# control.net
KiCad netlist of a schematic drawn in EAGLE
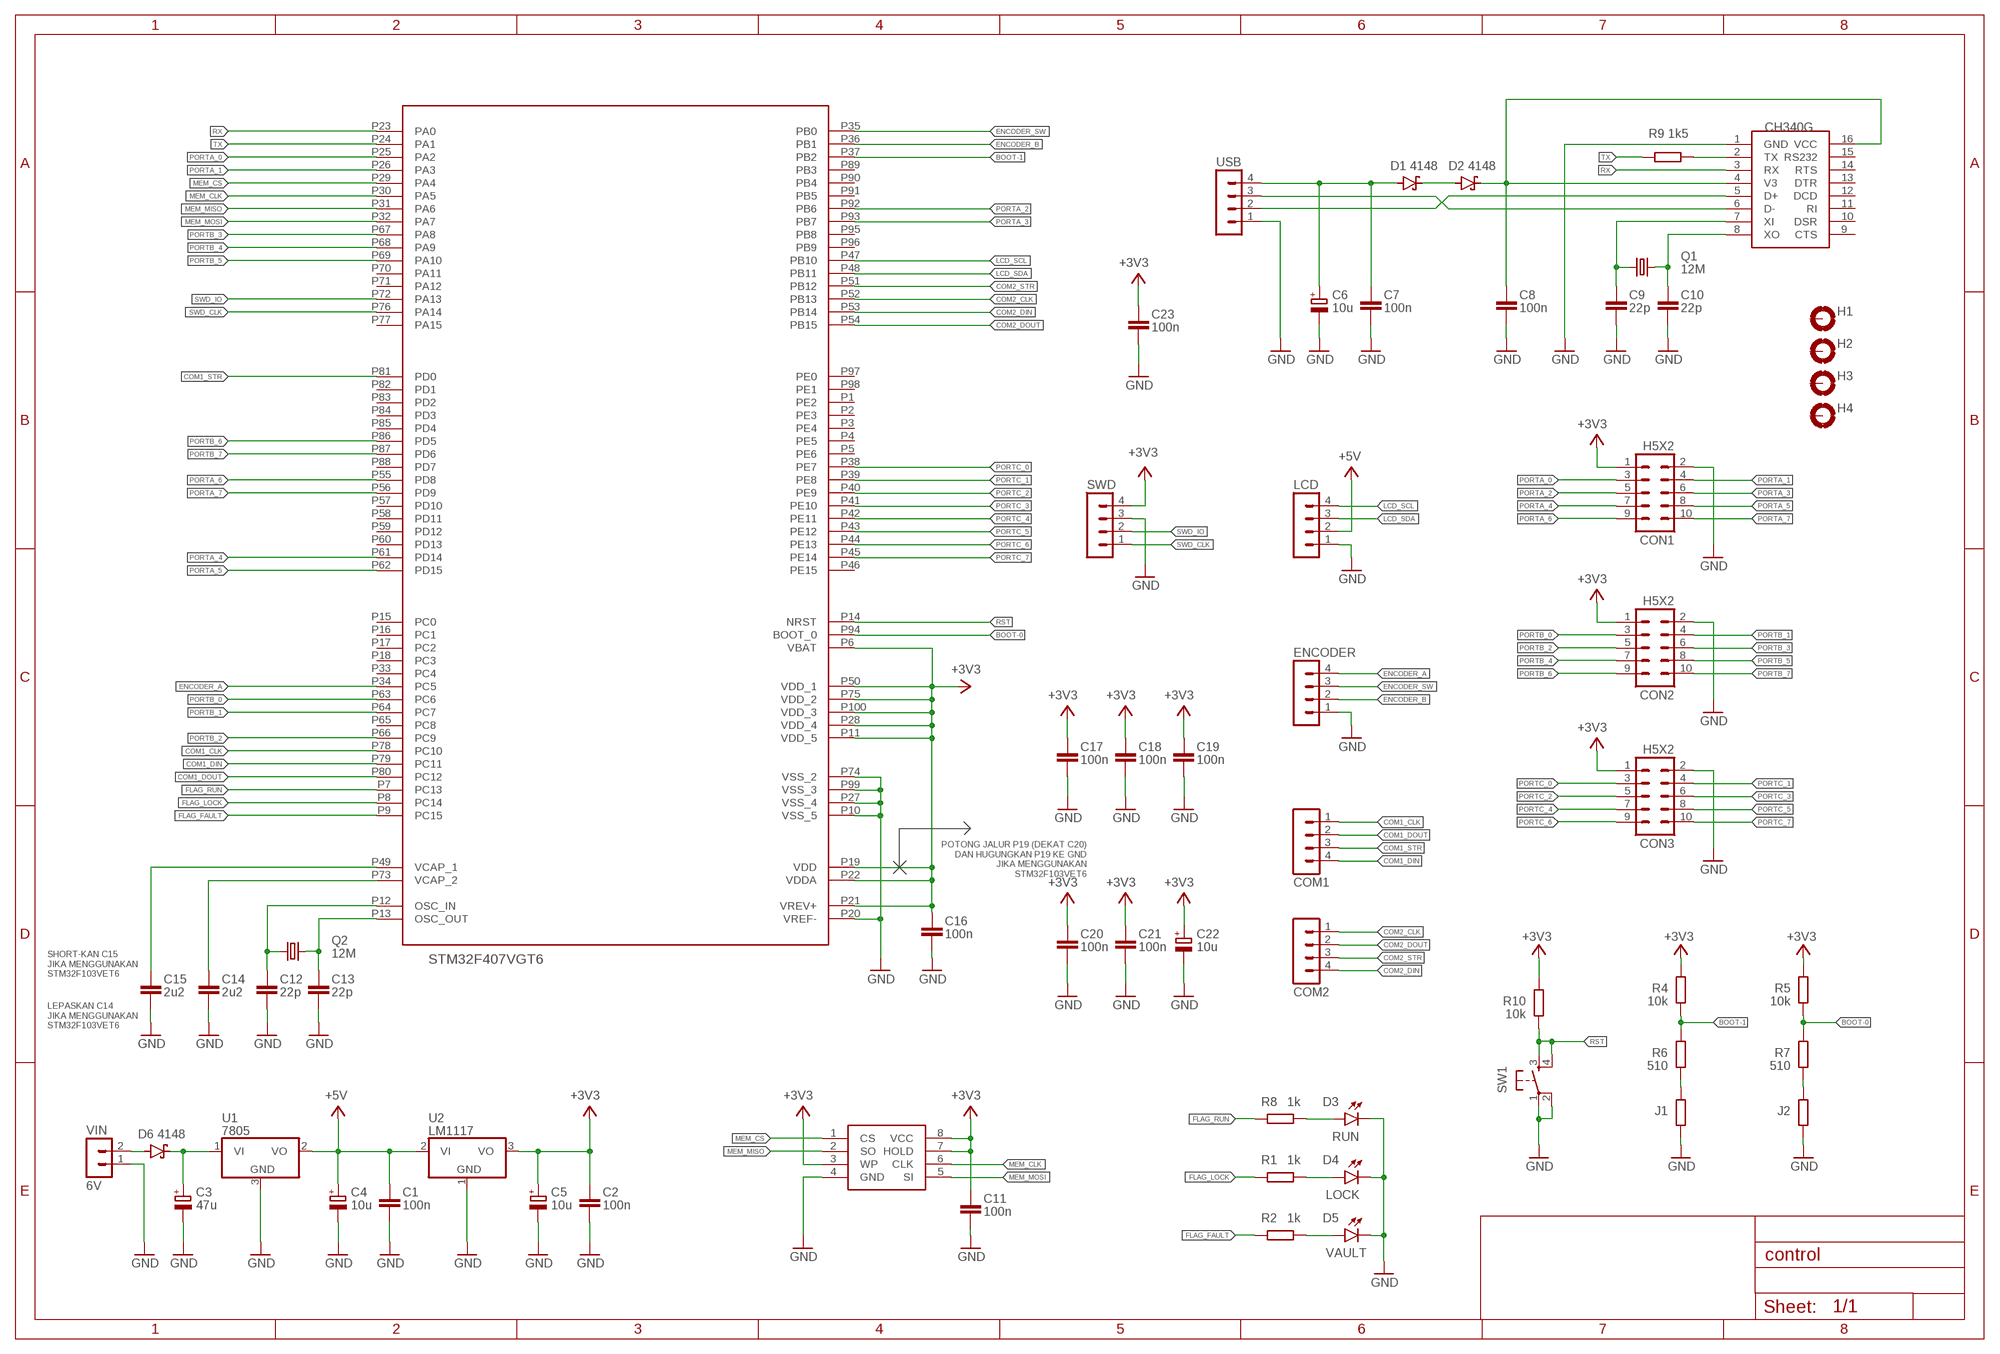
[diagram p0: schematic, sheet 1]

(export (version "E")
  (design (tool "Eeschema 10.0.6"))
  (components
    (comp (ref "C1")
      (value "100n")
      (footprint "eagle-import:0805")
      (libsource (lib "eagle-import") (part "CAP"))
    )
    (comp (ref "C2")
      (value "100n")
      (footprint "eagle-import:0805")
      (libsource (lib "eagle-import") (part "CAP"))
    )
    (comp (ref "C3")
      (value "47u")
      (footprint "eagle-import:E2,5-5")
      (libsource (lib "eagle-import") (part "C10UF"))
    )
    (comp (ref "C4")
      (value "10u")
      (footprint "eagle-import:E2,5-5")
      (libsource (lib "eagle-import") (part "C10UF"))
    )
    (comp (ref "C5")
      (value "10u")
      (footprint "eagle-import:E2,5-5")
      (libsource (lib "eagle-import") (part "C10UF"))
    )
    (comp (ref "C6")
      (value "10u")
      (footprint "eagle-import:E2,5-5")
      (libsource (lib "eagle-import") (part "C10UF"))
    )
    (comp (ref "C7")
      (value "100n")
      (footprint "eagle-import:0805")
      (libsource (lib "eagle-import") (part "CAP"))
    )
    (comp (ref "C8")
      (value "100n")
      (footprint "eagle-import:0805")
      (libsource (lib "eagle-import") (part "CAP"))
    )
    (comp (ref "C9")
      (value "22p")
      (footprint "eagle-import:0805")
      (libsource (lib "eagle-import") (part "CAP"))
    )
    (comp (ref "C10")
      (value "22p")
      (footprint "eagle-import:0805")
      (libsource (lib "eagle-import") (part "CAP"))
    )
    (comp (ref "C11")
      (value "100n")
      (footprint "eagle-import:0805")
      (libsource (lib "eagle-import") (part "CAP"))
    )
    (comp (ref "C12")
      (value "22p")
      (footprint "eagle-import:0805")
      (libsource (lib "eagle-import") (part "CAP"))
    )
    (comp (ref "C13")
      (value "22p")
      (footprint "eagle-import:0805")
      (libsource (lib "eagle-import") (part "CAP"))
    )
    (comp (ref "C14")
      (value "2u2")
      (footprint "eagle-import:0805")
      (libsource (lib "eagle-import") (part "CAP"))
    )
    (comp (ref "C15")
      (value "2u2")
      (footprint "eagle-import:0805")
      (libsource (lib "eagle-import") (part "CAP"))
    )
    (comp (ref "C16")
      (value "100n")
      (footprint "eagle-import:0805")
      (libsource (lib "eagle-import") (part "CAP"))
    )
    (comp (ref "C17")
      (value "100n")
      (footprint "eagle-import:0805")
      (libsource (lib "eagle-import") (part "CAP"))
    )
    (comp (ref "C18")
      (value "100n")
      (footprint "eagle-import:0805")
      (libsource (lib "eagle-import") (part "CAP"))
    )
    (comp (ref "C19")
      (value "100n")
      (footprint "eagle-import:0805")
      (libsource (lib "eagle-import") (part "CAP"))
    )
    (comp (ref "C20")
      (value "100n")
      (footprint "eagle-import:0805")
      (libsource (lib "eagle-import") (part "CAP"))
    )
    (comp (ref "C21")
      (value "100n")
      (footprint "eagle-import:0805")
      (libsource (lib "eagle-import") (part "CAP"))
    )
    (comp (ref "C22")
      (value "10u")
      (footprint "eagle-import:E2,5-5")
      (libsource (lib "eagle-import") (part "C10UF"))
    )
    (comp (ref "C23")
      (value "100n")
      (footprint "eagle-import:0805")
      (libsource (lib "eagle-import") (part "CAP"))
    )
    (comp (ref "COM1")
      (value "MOLEX-4")
      (footprint "eagle-import:6410-04")
      (libsource (lib "eagle-import") (part "MOLEX-4"))
    )
    (comp (ref "COM2")
      (value "MOLEX-4")
      (footprint "eagle-import:6410-04")
      (libsource (lib "eagle-import") (part "MOLEX-4"))
    )
    (comp (ref "CON1")
      (value "H5X2")
      (footprint "eagle-import:MA05-2")
      (libsource (lib "eagle-import") (part "H5X2"))
    )
    (comp (ref "CON2")
      (value "H5X2")
      (footprint "eagle-import:MA05-2")
      (libsource (lib "eagle-import") (part "H5X2"))
    )
    (comp (ref "CON3")
      (value "H5X2")
      (footprint "eagle-import:MA05-2")
      (libsource (lib "eagle-import") (part "H5X2"))
    )
    (comp (ref "D1")
      (value "4148")
      (footprint "eagle-import:DO35Z7")
      (libsource (lib "eagle-import") (part "1N5817"))
    )
    (comp (ref "D2")
      (value "4148")
      (footprint "eagle-import:DO35Z7")
      (libsource (lib "eagle-import") (part "1N5817"))
    )
    (comp (ref "D3")
      (value "RUN")
      (footprint "eagle-import:LED3MM")
      (libsource (lib "eagle-import") (part "LED3MM"))
    )
    (comp (ref "D4")
      (value "LOCK")
      (footprint "eagle-import:LED3MM")
      (libsource (lib "eagle-import") (part "LED3MM"))
    )
    (comp (ref "D5")
      (value "VAULT")
      (footprint "eagle-import:LED3MM")
      (libsource (lib "eagle-import") (part "LED3MM"))
    )
    (comp (ref "D6")
      (value "4148")
      (footprint "eagle-import:DO35Z7")
      (libsource (lib "eagle-import") (part "1N5817"))
    )
    (comp (ref "ENCODER")
      (value "MOLEX-4")
      (footprint "eagle-import:6410-04")
      (libsource (lib "eagle-import") (part "MOLEX-4"))
    )
    (comp (ref "H1")
      (value "MOUNT-PAD-ROUND3.0")
      (footprint "eagle-import:3,0-PAD")
      (libsource (lib "eagle-import") (part "MOUNT-PAD-ROUND3.0"))
    )
    (comp (ref "H2")
      (value "MOUNT-PAD-ROUND3.0")
      (footprint "eagle-import:3,0-PAD")
      (libsource (lib "eagle-import") (part "MOUNT-PAD-ROUND3.0"))
    )
    (comp (ref "H3")
      (value "MOUNT-PAD-ROUND3.0")
      (footprint "eagle-import:3,0-PAD")
      (libsource (lib "eagle-import") (part "MOUNT-PAD-ROUND3.0"))
    )
    (comp (ref "H4")
      (value "MOUNT-PAD-ROUND3.0")
      (footprint "eagle-import:3,0-PAD")
      (libsource (lib "eagle-import") (part "MOUNT-PAD-ROUND3.0"))
    )
    (comp (ref "J1")
      (value "10k")
      (footprint "eagle-import:0805")
      (libsource (lib "eagle-import") (part "RES"))
    )
    (comp (ref "J2")
      (value "10k")
      (footprint "eagle-import:0805")
      (libsource (lib "eagle-import") (part "RES"))
    )
    (comp (ref "LCD")
      (value "MOLEX-4")
      (footprint "eagle-import:6410-04")
      (libsource (lib "eagle-import") (part "MOLEX-4"))
    )
    (comp (ref "Q1")
      (value "12M")
      (footprint "eagle-import:HC49_S")
      (libsource (lib "eagle-import") (part "CRYSTAL"))
    )
    (comp (ref "Q2")
      (value "12M")
      (footprint "eagle-import:HC49_S")
      (libsource (lib "eagle-import") (part "CRYSTAL"))
    )
    (comp (ref "R1")
      (value "1k")
      (footprint "eagle-import:0805")
      (libsource (lib "eagle-import") (part "RES"))
    )
    (comp (ref "R2")
      (value "1k")
      (footprint "eagle-import:0805")
      (libsource (lib "eagle-import") (part "RES"))
    )
    (comp (ref "R4")
      (value "10k")
      (footprint "eagle-import:0805")
      (libsource (lib "eagle-import") (part "RES"))
    )
    (comp (ref "R5")
      (value "10k")
      (footprint "eagle-import:0805")
      (libsource (lib "eagle-import") (part "RES"))
    )
    (comp (ref "R6")
      (value "510")
      (footprint "eagle-import:0805")
      (libsource (lib "eagle-import") (part "RES"))
    )
    (comp (ref "R7")
      (value "510")
      (footprint "eagle-import:0805")
      (libsource (lib "eagle-import") (part "RES"))
    )
    (comp (ref "R8")
      (value "1k")
      (footprint "eagle-import:0805")
      (libsource (lib "eagle-import") (part "RES"))
    )
    (comp (ref "R9")
      (value "1k5")
      (footprint "eagle-import:0204_7")
      (libsource (lib "eagle-import") (part "R025"))
    )
    (comp (ref "R10")
      (value "10k")
      (footprint "eagle-import:0805")
      (libsource (lib "eagle-import") (part "RES"))
    )
    (comp (ref "SW1")
      (value "SW")
      (footprint "eagle-import:B3F-10XX")
      (libsource (lib "eagle-import") (part "SW"))
    )
    (comp (ref "SWD")
      (value "MOLEX-4")
      (footprint "eagle-import:6410-04")
      (libsource (lib "eagle-import") (part "MOLEX-4"))
    )
    (comp (ref "U$1")
      (value "CH340G")
      (footprint "eagle-import:SOIC16")
      (libsource (lib "eagle-import") (part "CH340G"))
    )
    (comp (ref "U1")
      (value "7805")
      (footprint "eagle-import:TO252")
      (libsource (lib "eagle-import") (part "7805"))
    )
    (comp (ref "U2")
      (value "LM1117")
      (footprint "eagle-import:TO252")
      (libsource (lib "eagle-import") (part "LM1117"))
    )
    (comp (ref "U3")
      (value "W25QXX")
      (footprint "eagle-import:SOP8")
      (libsource (lib "eagle-import") (part "W25QXX"))
    )
    (comp (ref "U4")
      (value "STM32F407")
      (footprint "eagle-import:LQFP100")
      (libsource (lib "eagle-import") (part "STM32F407"))
    )
    (comp (ref "USB")
      (value "MOLEX-4")
      (footprint "eagle-import:6410-04")
      (libsource (lib "eagle-import") (part "MOLEX-4"))
    )
    (comp (ref "VIN")
      (value "6V")
      (footprint "eagle-import:6410-02")
      (libsource (lib "eagle-import") (part "MOLEX-2"))
    )
  )
  (nets
    (net (code "1") (name "+3V3") (class "Default")
      (node (ref "C11") (pin "P$1") (pinfunction "1_P$1") (pintype "passive"))
      (node (ref "C16") (pin "P$1") (pinfunction "1_P$1") (pintype "passive"))
      (node (ref "C17") (pin "P$1") (pinfunction "1_P$1") (pintype "passive"))
      (node (ref "C18") (pin "P$1") (pinfunction "1_P$1") (pintype "passive"))
      (node (ref "C19") (pin "P$1") (pinfunction "1_P$1") (pintype "passive"))
      (node (ref "C2") (pin "P$1") (pinfunction "1_P$1") (pintype "passive"))
      (node (ref "C20") (pin "P$1") (pinfunction "1_P$1") (pintype "passive"))
      (node (ref "C21") (pin "P$1") (pinfunction "1_P$1") (pintype "passive"))
      (node (ref "C22") (pin "+") (pinfunction "+_+") (pintype "passive"))
      (node (ref "C23") (pin "P$1") (pinfunction "1_P$1") (pintype "passive"))
      (node (ref "C5") (pin "+") (pinfunction "+_+") (pintype "passive"))
      (node (ref "CON1") (pin "1") (pinfunction "1_1") (pintype "passive"))
      (node (ref "CON2") (pin "1") (pinfunction "1_1") (pintype "passive"))
      (node (ref "CON3") (pin "1") (pinfunction "1_1") (pintype "passive"))
      (node (ref "R10") (pin "P$2") (pinfunction "2_P$2") (pintype "passive"))
      (node (ref "R4") (pin "P$2") (pinfunction "2_P$2") (pintype "passive"))
      (node (ref "R5") (pin "P$2") (pinfunction "2_P$2") (pintype "passive"))
      (node (ref "SWD") (pin "4") (pinfunction "4_4") (pintype "passive"))
      (node (ref "U2") (pin "3") (pinfunction "VO_3") (pintype "passive"))
      (node (ref "U3") (pin "3") (pinfunction "WP_3") (pintype "bidirectional"))
      (node (ref "U3") (pin "7") (pinfunction "HOLD_7") (pintype "bidirectional"))
      (node (ref "U3") (pin "8") (pinfunction "VCC_8") (pintype "bidirectional"))
      (node (ref "U4") (pin "P100") (pinfunction "VDD_3_P100") (pintype "bidirectional"))
      (node (ref "U4") (pin "P11") (pinfunction "VDD_5_P11") (pintype "bidirectional"))
      (node (ref "U4") (pin "P19") (pinfunction "VDD_P19") (pintype "bidirectional"))
      (node (ref "U4") (pin "P21") (pinfunction "VREV+_P21") (pintype "bidirectional"))
      (node (ref "U4") (pin "P22") (pinfunction "VDDA_P22") (pintype "bidirectional"))
      (node (ref "U4") (pin "P28") (pinfunction "VDD_4_P28") (pintype "bidirectional"))
      (node (ref "U4") (pin "P50") (pinfunction "VDD_1_P50") (pintype "bidirectional"))
      (node (ref "U4") (pin "P6") (pinfunction "VBAT_P6") (pintype "bidirectional"))
      (node (ref "U4") (pin "P75") (pinfunction "VDD_2_P75") (pintype "bidirectional"))
    )
    (net (code "2") (name "+5V") (class "Default")
      (node (ref "C1") (pin "P$1") (pinfunction "1_P$1") (pintype "passive"))
      (node (ref "C4") (pin "+") (pinfunction "+_+") (pintype "passive"))
      (node (ref "LCD") (pin "2") (pinfunction "2_2") (pintype "passive"))
      (node (ref "U1") (pin "2") (pinfunction "VO_2") (pintype "passive"))
      (node (ref "U2") (pin "2") (pinfunction "VI_2") (pintype "input"))
    )
    (net (code "3") (name "BOOT-0") (class "Default")
      (node (ref "R5") (pin "P$1") (pinfunction "1_P$1") (pintype "passive"))
      (node (ref "R7") (pin "P$2") (pinfunction "2_P$2") (pintype "passive"))
      (node (ref "U4") (pin "P94") (pinfunction "BOOT_0_P94") (pintype "bidirectional"))
    )
    (net (code "4") (name "BOOT-1") (class "Default")
      (node (ref "R4") (pin "P$1") (pinfunction "1_P$1") (pintype "passive"))
      (node (ref "R6") (pin "P$2") (pinfunction "2_P$2") (pintype "passive"))
      (node (ref "U4") (pin "P37") (pinfunction "PB2_P37") (pintype "bidirectional"))
    )
    (net (code "5") (name "COM1_CLK") (class "Default")
      (node (ref "COM1") (pin "1") (pinfunction "1_1") (pintype "passive"))
      (node (ref "U4") (pin "P78") (pinfunction "PC10_P78") (pintype "bidirectional"))
    )
    (net (code "6") (name "COM1_DIN") (class "Default")
      (node (ref "COM1") (pin "4") (pinfunction "4_4") (pintype "passive"))
      (node (ref "U4") (pin "P79") (pinfunction "PC11_P79") (pintype "bidirectional"))
    )
    (net (code "7") (name "COM1_DOUT") (class "Default")
      (node (ref "COM1") (pin "2") (pinfunction "2_2") (pintype "passive"))
      (node (ref "U4") (pin "P80") (pinfunction "PC12_P80") (pintype "bidirectional"))
    )
    (net (code "8") (name "COM1_STR") (class "Default")
      (node (ref "COM1") (pin "3") (pinfunction "3_3") (pintype "passive"))
      (node (ref "U4") (pin "P81") (pinfunction "PD0_P81") (pintype "bidirectional"))
    )
    (net (code "9") (name "COM2_CLK") (class "Default")
      (node (ref "COM2") (pin "1") (pinfunction "1_1") (pintype "passive"))
      (node (ref "U4") (pin "P52") (pinfunction "PB13_P52") (pintype "bidirectional"))
    )
    (net (code "10") (name "COM2_DIN") (class "Default")
      (node (ref "COM2") (pin "4") (pinfunction "4_4") (pintype "passive"))
      (node (ref "U4") (pin "P53") (pinfunction "PB14_P53") (pintype "bidirectional"))
    )
    (net (code "11") (name "COM2_DOUT") (class "Default")
      (node (ref "COM2") (pin "2") (pinfunction "2_2") (pintype "passive"))
      (node (ref "U4") (pin "P54") (pinfunction "PB15_P54") (pintype "bidirectional"))
    )
    (net (code "12") (name "COM2_STR") (class "Default")
      (node (ref "COM2") (pin "3") (pinfunction "3_3") (pintype "passive"))
      (node (ref "U4") (pin "P51") (pinfunction "PB12_P51") (pintype "bidirectional"))
    )
    (net (code "13") (name "ENCODER_A") (class "Default")
      (node (ref "ENCODER") (pin "4") (pinfunction "4_4") (pintype "passive"))
      (node (ref "U4") (pin "P34") (pinfunction "PC5_P34") (pintype "bidirectional"))
    )
    (net (code "14") (name "ENCODER_B") (class "Default")
      (node (ref "ENCODER") (pin "2") (pinfunction "2_2") (pintype "passive"))
      (node (ref "U4") (pin "P36") (pinfunction "PB1_P36") (pintype "bidirectional"))
    )
    (net (code "15") (name "ENCODER_SW") (class "Default")
      (node (ref "ENCODER") (pin "3") (pinfunction "3_3") (pintype "passive"))
      (node (ref "U4") (pin "P35") (pinfunction "PB0_P35") (pintype "bidirectional"))
    )
    (net (code "16") (name "FLAG_FAULT") (class "Default")
      (node (ref "R2") (pin "P$2") (pinfunction "2_P$2") (pintype "passive"))
      (node (ref "U4") (pin "P9") (pinfunction "PC15_P9") (pintype "bidirectional"))
    )
    (net (code "17") (name "FLAG_LOCK") (class "Default")
      (node (ref "R1") (pin "P$2") (pinfunction "2_P$2") (pintype "passive"))
      (node (ref "U4") (pin "P8") (pinfunction "PC14_P8") (pintype "bidirectional"))
    )
    (net (code "18") (name "FLAG_RUN") (class "Default")
      (node (ref "R8") (pin "P$2") (pinfunction "2_P$2") (pintype "passive"))
      (node (ref "U4") (pin "P7") (pinfunction "PC13_P7") (pintype "bidirectional"))
    )
    (net (code "19") (name "GND") (class "Default")
      (node (ref "C1") (pin "P$2") (pinfunction "2_P$2") (pintype "passive"))
      (node (ref "C10") (pin "P$2") (pinfunction "2_P$2") (pintype "passive"))
      (node (ref "C11") (pin "P$2") (pinfunction "2_P$2") (pintype "passive"))
      (node (ref "C12") (pin "P$2") (pinfunction "2_P$2") (pintype "passive"))
      (node (ref "C13") (pin "P$2") (pinfunction "2_P$2") (pintype "passive"))
      (node (ref "C14") (pin "P$2") (pinfunction "2_P$2") (pintype "passive"))
      (node (ref "C15") (pin "P$2") (pinfunction "2_P$2") (pintype "passive"))
      (node (ref "C16") (pin "P$2") (pinfunction "2_P$2") (pintype "passive"))
      (node (ref "C17") (pin "P$2") (pinfunction "2_P$2") (pintype "passive"))
      (node (ref "C18") (pin "P$2") (pinfunction "2_P$2") (pintype "passive"))
      (node (ref "C19") (pin "P$2") (pinfunction "2_P$2") (pintype "passive"))
      (node (ref "C2") (pin "P$2") (pinfunction "2_P$2") (pintype "passive"))
      (node (ref "C20") (pin "P$2") (pinfunction "2_P$2") (pintype "passive"))
      (node (ref "C21") (pin "P$2") (pinfunction "2_P$2") (pintype "passive"))
      (node (ref "C22") (pin "-") (pinfunction "-_-") (pintype "passive"))
      (node (ref "C23") (pin "P$2") (pinfunction "2_P$2") (pintype "passive"))
      (node (ref "C3") (pin "-") (pinfunction "-_-") (pintype "passive"))
      (node (ref "C4") (pin "-") (pinfunction "-_-") (pintype "passive"))
      (node (ref "C5") (pin "-") (pinfunction "-_-") (pintype "passive"))
      (node (ref "C6") (pin "-") (pinfunction "-_-") (pintype "passive"))
      (node (ref "C7") (pin "P$2") (pinfunction "2_P$2") (pintype "passive"))
      (node (ref "C8") (pin "P$2") (pinfunction "2_P$2") (pintype "passive"))
      (node (ref "C9") (pin "P$2") (pinfunction "2_P$2") (pintype "passive"))
      (node (ref "CON1") (pin "2") (pinfunction "2_2") (pintype "passive"))
      (node (ref "CON2") (pin "2") (pinfunction "2_2") (pintype "passive"))
      (node (ref "CON3") (pin "2") (pinfunction "2_2") (pintype "passive"))
      (node (ref "D3") (pin "K") (pinfunction "C_K") (pintype "passive"))
      (node (ref "D4") (pin "K") (pinfunction "C_K") (pintype "passive"))
      (node (ref "D5") (pin "K") (pinfunction "C_K") (pintype "passive"))
      (node (ref "ENCODER") (pin "1") (pinfunction "1_1") (pintype "passive"))
      (node (ref "J1") (pin "P$1") (pinfunction "1_P$1") (pintype "passive"))
      (node (ref "J2") (pin "P$1") (pinfunction "1_P$1") (pintype "passive"))
      (node (ref "LCD") (pin "1") (pinfunction "1_1") (pintype "passive"))
      (node (ref "SW1") (pin "1") (pinfunction "P_1") (pintype "passive"))
      (node (ref "SW1") (pin "2") (pinfunction "P1_2") (pintype "passive"))
      (node (ref "SWD") (pin "3") (pinfunction "3_3") (pintype "passive"))
      (node (ref "U$1") (pin "1") (pinfunction "GND_1") (pintype "bidirectional"))
      (node (ref "U1") (pin "3") (pinfunction "GND_3") (pintype "passive"))
      (node (ref "U2") (pin "1") (pinfunction "GND_1") (pintype "passive"))
      (node (ref "U3") (pin "4") (pinfunction "GND_4") (pintype "bidirectional"))
      (node (ref "U4") (pin "P10") (pinfunction "VSS_5_P10") (pintype "bidirectional"))
      (node (ref "U4") (pin "P20") (pinfunction "VREF-_P20") (pintype "bidirectional"))
      (node (ref "U4") (pin "P27") (pinfunction "VSS_4_P27") (pintype "bidirectional"))
      (node (ref "U4") (pin "P74") (pinfunction "VSS_2_P74") (pintype "bidirectional"))
      (node (ref "U4") (pin "P99") (pinfunction "VSS_3_P99") (pintype "bidirectional"))
      (node (ref "USB") (pin "1") (pinfunction "1_1") (pintype "passive"))
      (node (ref "VIN") (pin "1") (pinfunction "1_1") (pintype "passive"))
    )
    (net (code "20") (name "LCD_SCL") (class "Default")
      (node (ref "LCD") (pin "4") (pinfunction "4_4") (pintype "passive"))
      (node (ref "U4") (pin "P47") (pinfunction "PB10_P47") (pintype "bidirectional"))
    )
    (net (code "21") (name "LCD_SDA") (class "Default")
      (node (ref "LCD") (pin "3") (pinfunction "3_3") (pintype "passive"))
      (node (ref "U4") (pin "P48") (pinfunction "PB11_P48") (pintype "bidirectional"))
    )
    (net (code "22") (name "MEM_CLK") (class "Default")
      (node (ref "U3") (pin "6") (pinfunction "CLK_6") (pintype "bidirectional"))
      (node (ref "U4") (pin "P30") (pinfunction "PA5_P30") (pintype "bidirectional"))
    )
    (net (code "23") (name "MEM_CS") (class "Default")
      (node (ref "U3") (pin "1") (pinfunction "CS_1") (pintype "bidirectional"))
      (node (ref "U4") (pin "P29") (pinfunction "PA4_P29") (pintype "bidirectional"))
    )
    (net (code "24") (name "MEM_MISO") (class "Default")
      (node (ref "U3") (pin "2") (pinfunction "SO_2") (pintype "bidirectional"))
      (node (ref "U4") (pin "P31") (pinfunction "PA6_P31") (pintype "bidirectional"))
    )
    (net (code "25") (name "MEM_MOSI") (class "Default")
      (node (ref "U3") (pin "5") (pinfunction "SI_5") (pintype "bidirectional"))
      (node (ref "U4") (pin "P32") (pinfunction "PA7_P32") (pintype "bidirectional"))
    )
    (net (code "26") (name "Net-(C7-1)") (class "Default")
      (node (ref "C6") (pin "+") (pinfunction "+_+") (pintype "passive"))
      (node (ref "C7") (pin "P$1") (pinfunction "1_P$1") (pintype "passive"))
      (node (ref "D1") (pin "A") (pinfunction "A_A") (pintype "passive"))
      (node (ref "USB") (pin "4") (pinfunction "4_4") (pintype "passive"))
    )
    (net (code "27") (name "Net-(C8-1)") (class "Default")
      (node (ref "C8") (pin "P$1") (pinfunction "1_P$1") (pintype "passive"))
      (node (ref "D2") (pin "C") (pinfunction "C_C") (pintype "passive"))
      (node (ref "U$1") (pin "16") (pinfunction "VCC_16") (pintype "bidirectional"))
      (node (ref "U$1") (pin "4") (pinfunction "V3_4") (pintype "bidirectional"))
    )
    (net (code "28") (name "Net-(C9-1)") (class "Default")
      (node (ref "C9") (pin "P$1") (pinfunction "1_P$1") (pintype "passive"))
      (node (ref "Q1") (pin "1") (pinfunction "1_1") (pintype "passive"))
      (node (ref "U$1") (pin "7") (pinfunction "XI_7") (pintype "bidirectional"))
    )
    (net (code "29") (name "Net-(C10-1)") (class "Default")
      (node (ref "C10") (pin "P$1") (pinfunction "1_P$1") (pintype "passive"))
      (node (ref "Q1") (pin "2") (pinfunction "2_2") (pintype "passive"))
      (node (ref "U$1") (pin "8") (pinfunction "XO_8") (pintype "bidirectional"))
    )
    (net (code "30") (name "Net-(C12-1)") (class "Default")
      (node (ref "C12") (pin "P$1") (pinfunction "1_P$1") (pintype "passive"))
      (node (ref "Q2") (pin "1") (pinfunction "1_1") (pintype "passive"))
      (node (ref "U4") (pin "P12") (pinfunction "OSC_IN_P12") (pintype "bidirectional"))
    )
    (net (code "31") (name "Net-(C13-1)") (class "Default")
      (node (ref "C13") (pin "P$1") (pinfunction "1_P$1") (pintype "passive"))
      (node (ref "Q2") (pin "2") (pinfunction "2_2") (pintype "passive"))
      (node (ref "U4") (pin "P13") (pinfunction "OSC_OUT_P13") (pintype "bidirectional"))
    )
    (net (code "32") (name "Net-(C14-1)") (class "Default")
      (node (ref "C14") (pin "P$1") (pinfunction "1_P$1") (pintype "passive"))
      (node (ref "U4") (pin "P73") (pinfunction "VCAP_2_P73") (pintype "bidirectional"))
    )
    (net (code "33") (name "Net-(C15-1)") (class "Default")
      (node (ref "C15") (pin "P$1") (pinfunction "1_P$1") (pintype "passive"))
      (node (ref "U4") (pin "P49") (pinfunction "VCAP_1_P49") (pintype "bidirectional"))
    )
    (net (code "34") (name "Net-(D1-PadC)") (class "Default")
      (node (ref "D1") (pin "C") (pinfunction "C_C") (pintype "passive"))
      (node (ref "D2") (pin "A") (pinfunction "A_A") (pintype "passive"))
    )
    (net (code "35") (name "Net-(D6-PadA)") (class "Default")
      (node (ref "D6") (pin "A") (pinfunction "A_A") (pintype "passive"))
      (node (ref "VIN") (pin "2") (pinfunction "2_2") (pintype "passive"))
    )
    (net (code "36") (name "Net-(J1-2)") (class "Default")
      (node (ref "J1") (pin "P$2") (pinfunction "2_P$2") (pintype "passive"))
      (node (ref "R6") (pin "P$1") (pinfunction "1_P$1") (pintype "passive"))
    )
    (net (code "37") (name "Net-(J2-2)") (class "Default")
      (node (ref "J2") (pin "P$2") (pinfunction "2_P$2") (pintype "passive"))
      (node (ref "R7") (pin "P$1") (pinfunction "1_P$1") (pintype "passive"))
    )
    (net (code "38") (name "Net-(R1-1)") (class "Default")
      (node (ref "D4") (pin "A") (pinfunction "A_A") (pintype "passive"))
      (node (ref "R1") (pin "P$1") (pinfunction "1_P$1") (pintype "passive"))
    )
    (net (code "39") (name "Net-(R2-1)") (class "Default")
      (node (ref "D5") (pin "A") (pinfunction "A_A") (pintype "passive"))
      (node (ref "R2") (pin "P$1") (pinfunction "1_P$1") (pintype "passive"))
    )
    (net (code "40") (name "Net-(R8-1)") (class "Default")
      (node (ref "D3") (pin "A") (pinfunction "A_A") (pintype "passive"))
      (node (ref "R8") (pin "P$1") (pinfunction "1_P$1") (pintype "passive"))
    )
    (net (code "41") (name "Net-(U$1-D+)") (class "Default")
      (node (ref "U$1") (pin "5") (pinfunction "D+_5") (pintype "bidirectional"))
      (node (ref "USB") (pin "2") (pinfunction "2_2") (pintype "passive"))
    )
    (net (code "42") (name "Net-(U$1-D-)") (class "Default")
      (node (ref "U$1") (pin "6") (pinfunction "D-_6") (pintype "bidirectional"))
      (node (ref "USB") (pin "3") (pinfunction "3_3") (pintype "passive"))
    )
    (net (code "43") (name "Net-(U$1-TX)") (class "Default")
      (node (ref "R9") (pin "2") (pinfunction "2_2") (pintype "passive"))
      (node (ref "U$1") (pin "2") (pinfunction "TX_2") (pintype "bidirectional"))
    )
    (net (code "44") (name "Net-(U1-VI)") (class "Default")
      (node (ref "C3") (pin "+") (pinfunction "+_+") (pintype "passive"))
      (node (ref "D6") (pin "C") (pinfunction "C_C") (pintype "passive"))
      (node (ref "U1") (pin "1") (pinfunction "VI_1") (pintype "input"))
    )
    (net (code "45") (name "PORTA_0") (class "Default")
      (node (ref "CON1") (pin "3") (pinfunction "3_3") (pintype "passive"))
      (node (ref "U4") (pin "P25") (pinfunction "PA2_P25") (pintype "bidirectional"))
    )
    (net (code "46") (name "PORTA_1") (class "Default")
      (node (ref "CON1") (pin "4") (pinfunction "4_4") (pintype "passive"))
      (node (ref "U4") (pin "P26") (pinfunction "PA3_P26") (pintype "bidirectional"))
    )
    (net (code "47") (name "PORTA_2") (class "Default")
      (node (ref "CON1") (pin "5") (pinfunction "5_5") (pintype "passive"))
      (node (ref "U4") (pin "P92") (pinfunction "PB6_P92") (pintype "bidirectional"))
    )
    (net (code "48") (name "PORTA_3") (class "Default")
      (node (ref "CON1") (pin "6") (pinfunction "6_6") (pintype "passive"))
      (node (ref "U4") (pin "P93") (pinfunction "PB7_P93") (pintype "bidirectional"))
    )
    (net (code "49") (name "PORTA_4") (class "Default")
      (node (ref "CON1") (pin "7") (pinfunction "7_7") (pintype "passive"))
      (node (ref "U4") (pin "P61") (pinfunction "PD14_P61") (pintype "bidirectional"))
    )
    (net (code "50") (name "PORTA_5") (class "Default")
      (node (ref "CON1") (pin "8") (pinfunction "8_8") (pintype "passive"))
      (node (ref "U4") (pin "P62") (pinfunction "PD15_P62") (pintype "bidirectional"))
    )
    (net (code "51") (name "PORTA_6") (class "Default")
      (node (ref "CON1") (pin "9") (pinfunction "9_9") (pintype "passive"))
      (node (ref "U4") (pin "P55") (pinfunction "PD8_P55") (pintype "bidirectional"))
    )
    (net (code "52") (name "PORTA_7") (class "Default")
      (node (ref "CON1") (pin "10") (pinfunction "10_10") (pintype "passive"))
      (node (ref "U4") (pin "P56") (pinfunction "PD9_P56") (pintype "bidirectional"))
    )
    (net (code "53") (name "PORTB_0") (class "Default")
      (node (ref "CON2") (pin "3") (pinfunction "3_3") (pintype "passive"))
      (node (ref "U4") (pin "P63") (pinfunction "PC6_P63") (pintype "bidirectional"))
    )
    (net (code "54") (name "PORTB_1") (class "Default")
      (node (ref "CON2") (pin "4") (pinfunction "4_4") (pintype "passive"))
      (node (ref "U4") (pin "P64") (pinfunction "PC7_P64") (pintype "bidirectional"))
    )
    (net (code "55") (name "PORTB_2") (class "Default")
      (node (ref "CON2") (pin "5") (pinfunction "5_5") (pintype "passive"))
      (node (ref "U4") (pin "P66") (pinfunction "PC9_P66") (pintype "bidirectional"))
    )
    (net (code "56") (name "PORTB_3") (class "Default")
      (node (ref "CON2") (pin "6") (pinfunction "6_6") (pintype "passive"))
      (node (ref "U4") (pin "P67") (pinfunction "PA8_P67") (pintype "bidirectional"))
    )
    (net (code "57") (name "PORTB_4") (class "Default")
      (node (ref "CON2") (pin "7") (pinfunction "7_7") (pintype "passive"))
      (node (ref "U4") (pin "P68") (pinfunction "PA9_P68") (pintype "bidirectional"))
    )
    (net (code "58") (name "PORTB_5") (class "Default")
      (node (ref "CON2") (pin "8") (pinfunction "8_8") (pintype "passive"))
      (node (ref "U4") (pin "P69") (pinfunction "PA10_P69") (pintype "bidirectional"))
    )
    (net (code "59") (name "PORTB_6") (class "Default")
      (node (ref "CON2") (pin "9") (pinfunction "9_9") (pintype "passive"))
      (node (ref "U4") (pin "P86") (pinfunction "PD5_P86") (pintype "bidirectional"))
    )
    (net (code "60") (name "PORTB_7") (class "Default")
      (node (ref "CON2") (pin "10") (pinfunction "10_10") (pintype "passive"))
      (node (ref "U4") (pin "P87") (pinfunction "PD6_P87") (pintype "bidirectional"))
    )
    (net (code "61") (name "PORTC_0") (class "Default")
      (node (ref "CON3") (pin "3") (pinfunction "3_3") (pintype "passive"))
      (node (ref "U4") (pin "P38") (pinfunction "PE7_P38") (pintype "bidirectional"))
    )
    (net (code "62") (name "PORTC_1") (class "Default")
      (node (ref "CON3") (pin "4") (pinfunction "4_4") (pintype "passive"))
      (node (ref "U4") (pin "P39") (pinfunction "PE8_P39") (pintype "bidirectional"))
    )
    (net (code "63") (name "PORTC_2") (class "Default")
      (node (ref "CON3") (pin "5") (pinfunction "5_5") (pintype "passive"))
      (node (ref "U4") (pin "P40") (pinfunction "PE9_P40") (pintype "bidirectional"))
    )
    (net (code "64") (name "PORTC_3") (class "Default")
      (node (ref "CON3") (pin "6") (pinfunction "6_6") (pintype "passive"))
      (node (ref "U4") (pin "P41") (pinfunction "PE10_P41") (pintype "bidirectional"))
    )
    (net (code "65") (name "PORTC_4") (class "Default")
      (node (ref "CON3") (pin "7") (pinfunction "7_7") (pintype "passive"))
      (node (ref "U4") (pin "P42") (pinfunction "PE11_P42") (pintype "bidirectional"))
    )
    (net (code "66") (name "PORTC_5") (class "Default")
      (node (ref "CON3") (pin "8") (pinfunction "8_8") (pintype "passive"))
      (node (ref "U4") (pin "P43") (pinfunction "PE12_P43") (pintype "bidirectional"))
    )
    (net (code "67") (name "PORTC_6") (class "Default")
      (node (ref "CON3") (pin "9") (pinfunction "9_9") (pintype "passive"))
      (node (ref "U4") (pin "P44") (pinfunction "PE13_P44") (pintype "bidirectional"))
    )
    (net (code "68") (name "PORTC_7") (class "Default")
      (node (ref "CON3") (pin "10") (pinfunction "10_10") (pintype "passive"))
      (node (ref "U4") (pin "P45") (pinfunction "PE14_P45") (pintype "bidirectional"))
    )
    (net (code "69") (name "RST") (class "Default")
      (node (ref "R10") (pin "P$1") (pinfunction "1_P$1") (pintype "passive"))
      (node (ref "SW1") (pin "3") (pinfunction "S_3") (pintype "passive"))
      (node (ref "SW1") (pin "4") (pinfunction "S1_4") (pintype "passive"))
      (node (ref "U4") (pin "P14") (pinfunction "NRST_P14") (pintype "bidirectional"))
    )
    (net (code "70") (name "RX") (class "Default")
      (node (ref "U$1") (pin "3") (pinfunction "RX_3") (pintype "bidirectional"))
      (node (ref "U4") (pin "P23") (pinfunction "PA0_P23") (pintype "bidirectional"))
    )
    (net (code "71") (name "SWD_CLK") (class "Default")
      (node (ref "SWD") (pin "1") (pinfunction "1_1") (pintype "passive"))
      (node (ref "U4") (pin "P76") (pinfunction "PA14_P76") (pintype "bidirectional"))
    )
    (net (code "72") (name "SWD_IO") (class "Default")
      (node (ref "SWD") (pin "2") (pinfunction "2_2") (pintype "passive"))
      (node (ref "U4") (pin "P72") (pinfunction "PA13_P72") (pintype "bidirectional"))
    )
    (net (code "73") (name "TX") (class "Default")
      (node (ref "R9") (pin "1") (pinfunction "1_1") (pintype "passive"))
      (node (ref "U4") (pin "P24") (pinfunction "PA1_P24") (pintype "bidirectional"))
    )
    (net (code "74") (name "unconnected-(H1-MOUNT-PadB3,0)") (class "Default")
      (node (ref "H1") (pin "B3,0") (pinfunction "MOUNT_B3,0") (pintype "passive"))
    )
    (net (code "75") (name "unconnected-(H2-MOUNT-PadB3,0)") (class "Default")
      (node (ref "H2") (pin "B3,0") (pinfunction "MOUNT_B3,0") (pintype "passive"))
    )
    (net (code "76") (name "unconnected-(H3-MOUNT-PadB3,0)") (class "Default")
      (node (ref "H3") (pin "B3,0") (pinfunction "MOUNT_B3,0") (pintype "passive"))
    )
    (net (code "77") (name "unconnected-(H4-MOUNT-PadB3,0)") (class "Default")
      (node (ref "H4") (pin "B3,0") (pinfunction "MOUNT_B3,0") (pintype "passive"))
    )
    (net (code "78") (name "unconnected-(U$1-CTS-Pad9)") (class "Default")
      (node (ref "U$1") (pin "9") (pinfunction "CTS_9") (pintype "bidirectional"))
    )
    (net (code "79") (name "unconnected-(U$1-DCD-Pad12)") (class "Default")
      (node (ref "U$1") (pin "12") (pinfunction "DCD_12") (pintype "bidirectional"))
    )
    (net (code "80") (name "unconnected-(U$1-DSR-Pad10)") (class "Default")
      (node (ref "U$1") (pin "10") (pinfunction "DSR_10") (pintype "bidirectional"))
    )
    (net (code "81") (name "unconnected-(U$1-DTR-Pad13)") (class "Default")
      (node (ref "U$1") (pin "13") (pinfunction "DTR_13") (pintype "bidirectional"))
    )
    (net (code "82") (name "unconnected-(U$1-RI-Pad11)") (class "Default")
      (node (ref "U$1") (pin "11") (pinfunction "RI_11") (pintype "bidirectional"))
    )
    (net (code "83") (name "unconnected-(U$1-RS232-Pad15)") (class "Default")
      (node (ref "U$1") (pin "15") (pinfunction "RS232_15") (pintype "bidirectional"))
    )
    (net (code "84") (name "unconnected-(U$1-RTS-Pad14)") (class "Default")
      (node (ref "U$1") (pin "14") (pinfunction "RTS_14") (pintype "bidirectional"))
    )
    (net (code "85") (name "unconnected-(U4-PA11-PadP70)") (class "Default")
      (node (ref "U4") (pin "P70") (pinfunction "PA11_P70") (pintype "bidirectional"))
    )
    (net (code "86") (name "unconnected-(U4-PA12-PadP71)") (class "Default")
      (node (ref "U4") (pin "P71") (pinfunction "PA12_P71") (pintype "bidirectional"))
    )
    (net (code "87") (name "unconnected-(U4-PA15-PadP77)") (class "Default")
      (node (ref "U4") (pin "P77") (pinfunction "PA15_P77") (pintype "bidirectional"))
    )
    (net (code "88") (name "unconnected-(U4-PB3-PadP89)") (class "Default")
      (node (ref "U4") (pin "P89") (pinfunction "PB3_P89") (pintype "bidirectional"))
    )
    (net (code "89") (name "unconnected-(U4-PB4-PadP90)") (class "Default")
      (node (ref "U4") (pin "P90") (pinfunction "PB4_P90") (pintype "bidirectional"))
    )
    (net (code "90") (name "unconnected-(U4-PB5-PadP91)") (class "Default")
      (node (ref "U4") (pin "P91") (pinfunction "PB5_P91") (pintype "bidirectional"))
    )
    (net (code "91") (name "unconnected-(U4-PB8-PadP95)") (class "Default")
      (node (ref "U4") (pin "P95") (pinfunction "PB8_P95") (pintype "bidirectional"))
    )
    (net (code "92") (name "unconnected-(U4-PB9-PadP96)") (class "Default")
      (node (ref "U4") (pin "P96") (pinfunction "PB9_P96") (pintype "bidirectional"))
    )
    (net (code "93") (name "unconnected-(U4-PC0-PadP15)") (class "Default")
      (node (ref "U4") (pin "P15") (pinfunction "PC0_P15") (pintype "bidirectional"))
    )
    (net (code "94") (name "unconnected-(U4-PC1-PadP16)") (class "Default")
      (node (ref "U4") (pin "P16") (pinfunction "PC1_P16") (pintype "bidirectional"))
    )
    (net (code "95") (name "unconnected-(U4-PC2-PadP17)") (class "Default")
      (node (ref "U4") (pin "P17") (pinfunction "PC2_P17") (pintype "bidirectional"))
    )
    (net (code "96") (name "unconnected-(U4-PC3-PadP18)") (class "Default")
      (node (ref "U4") (pin "P18") (pinfunction "PC3_P18") (pintype "bidirectional"))
    )
    (net (code "97") (name "unconnected-(U4-PC4-PadP33)") (class "Default")
      (node (ref "U4") (pin "P33") (pinfunction "PC4_P33") (pintype "bidirectional"))
    )
    (net (code "98") (name "unconnected-(U4-PC8-PadP65)") (class "Default")
      (node (ref "U4") (pin "P65") (pinfunction "PC8_P65") (pintype "bidirectional"))
    )
    (net (code "99") (name "unconnected-(U4-PD1-PadP82)") (class "Default")
      (node (ref "U4") (pin "P82") (pinfunction "PD1_P82") (pintype "bidirectional"))
    )
    (net (code "100") (name "unconnected-(U4-PD2-PadP83)") (class "Default")
      (node (ref "U4") (pin "P83") (pinfunction "PD2_P83") (pintype "bidirectional"))
    )
    (net (code "101") (name "unconnected-(U4-PD3-PadP84)") (class "Default")
      (node (ref "U4") (pin "P84") (pinfunction "PD3_P84") (pintype "bidirectional"))
    )
    (net (code "102") (name "unconnected-(U4-PD4-PadP85)") (class "Default")
      (node (ref "U4") (pin "P85") (pinfunction "PD4_P85") (pintype "bidirectional"))
    )
    (net (code "103") (name "unconnected-(U4-PD7-PadP88)") (class "Default")
      (node (ref "U4") (pin "P88") (pinfunction "PD7_P88") (pintype "bidirectional"))
    )
    (net (code "104") (name "unconnected-(U4-PD10-PadP57)") (class "Default")
      (node (ref "U4") (pin "P57") (pinfunction "PD10_P57") (pintype "bidirectional"))
    )
    (net (code "105") (name "unconnected-(U4-PD11-PadP58)") (class "Default")
      (node (ref "U4") (pin "P58") (pinfunction "PD11_P58") (pintype "bidirectional"))
    )
    (net (code "106") (name "unconnected-(U4-PD12-PadP59)") (class "Default")
      (node (ref "U4") (pin "P59") (pinfunction "PD12_P59") (pintype "bidirectional"))
    )
    (net (code "107") (name "unconnected-(U4-PD13-PadP60)") (class "Default")
      (node (ref "U4") (pin "P60") (pinfunction "PD13_P60") (pintype "bidirectional"))
    )
    (net (code "108") (name "unconnected-(U4-PE0-PadP97)") (class "Default")
      (node (ref "U4") (pin "P97") (pinfunction "PE0_P97") (pintype "bidirectional"))
    )
    (net (code "109") (name "unconnected-(U4-PE1-PadP98)") (class "Default")
      (node (ref "U4") (pin "P98") (pinfunction "PE1_P98") (pintype "bidirectional"))
    )
    (net (code "110") (name "unconnected-(U4-PE2-PadP1)") (class "Default")
      (node (ref "U4") (pin "P1") (pinfunction "PE2_P1") (pintype "bidirectional"))
    )
    (net (code "111") (name "unconnected-(U4-PE3-PadP2)") (class "Default")
      (node (ref "U4") (pin "P2") (pinfunction "PE3_P2") (pintype "bidirectional"))
    )
    (net (code "112") (name "unconnected-(U4-PE4-PadP3)") (class "Default")
      (node (ref "U4") (pin "P3") (pinfunction "PE4_P3") (pintype "bidirectional"))
    )
    (net (code "113") (name "unconnected-(U4-PE5-PadP4)") (class "Default")
      (node (ref "U4") (pin "P4") (pinfunction "PE5_P4") (pintype "bidirectional"))
    )
    (net (code "114") (name "unconnected-(U4-PE6-PadP5)") (class "Default")
      (node (ref "U4") (pin "P5") (pinfunction "PE6_P5") (pintype "bidirectional"))
    )
    (net (code "115") (name "unconnected-(U4-PE15-PadP46)") (class "Default")
      (node (ref "U4") (pin "P46") (pinfunction "PE15_P46") (pintype "bidirectional"))
    )
  )
)
